# cndy-001.net
KiCad netlist of a schematic drawn in EAGLE
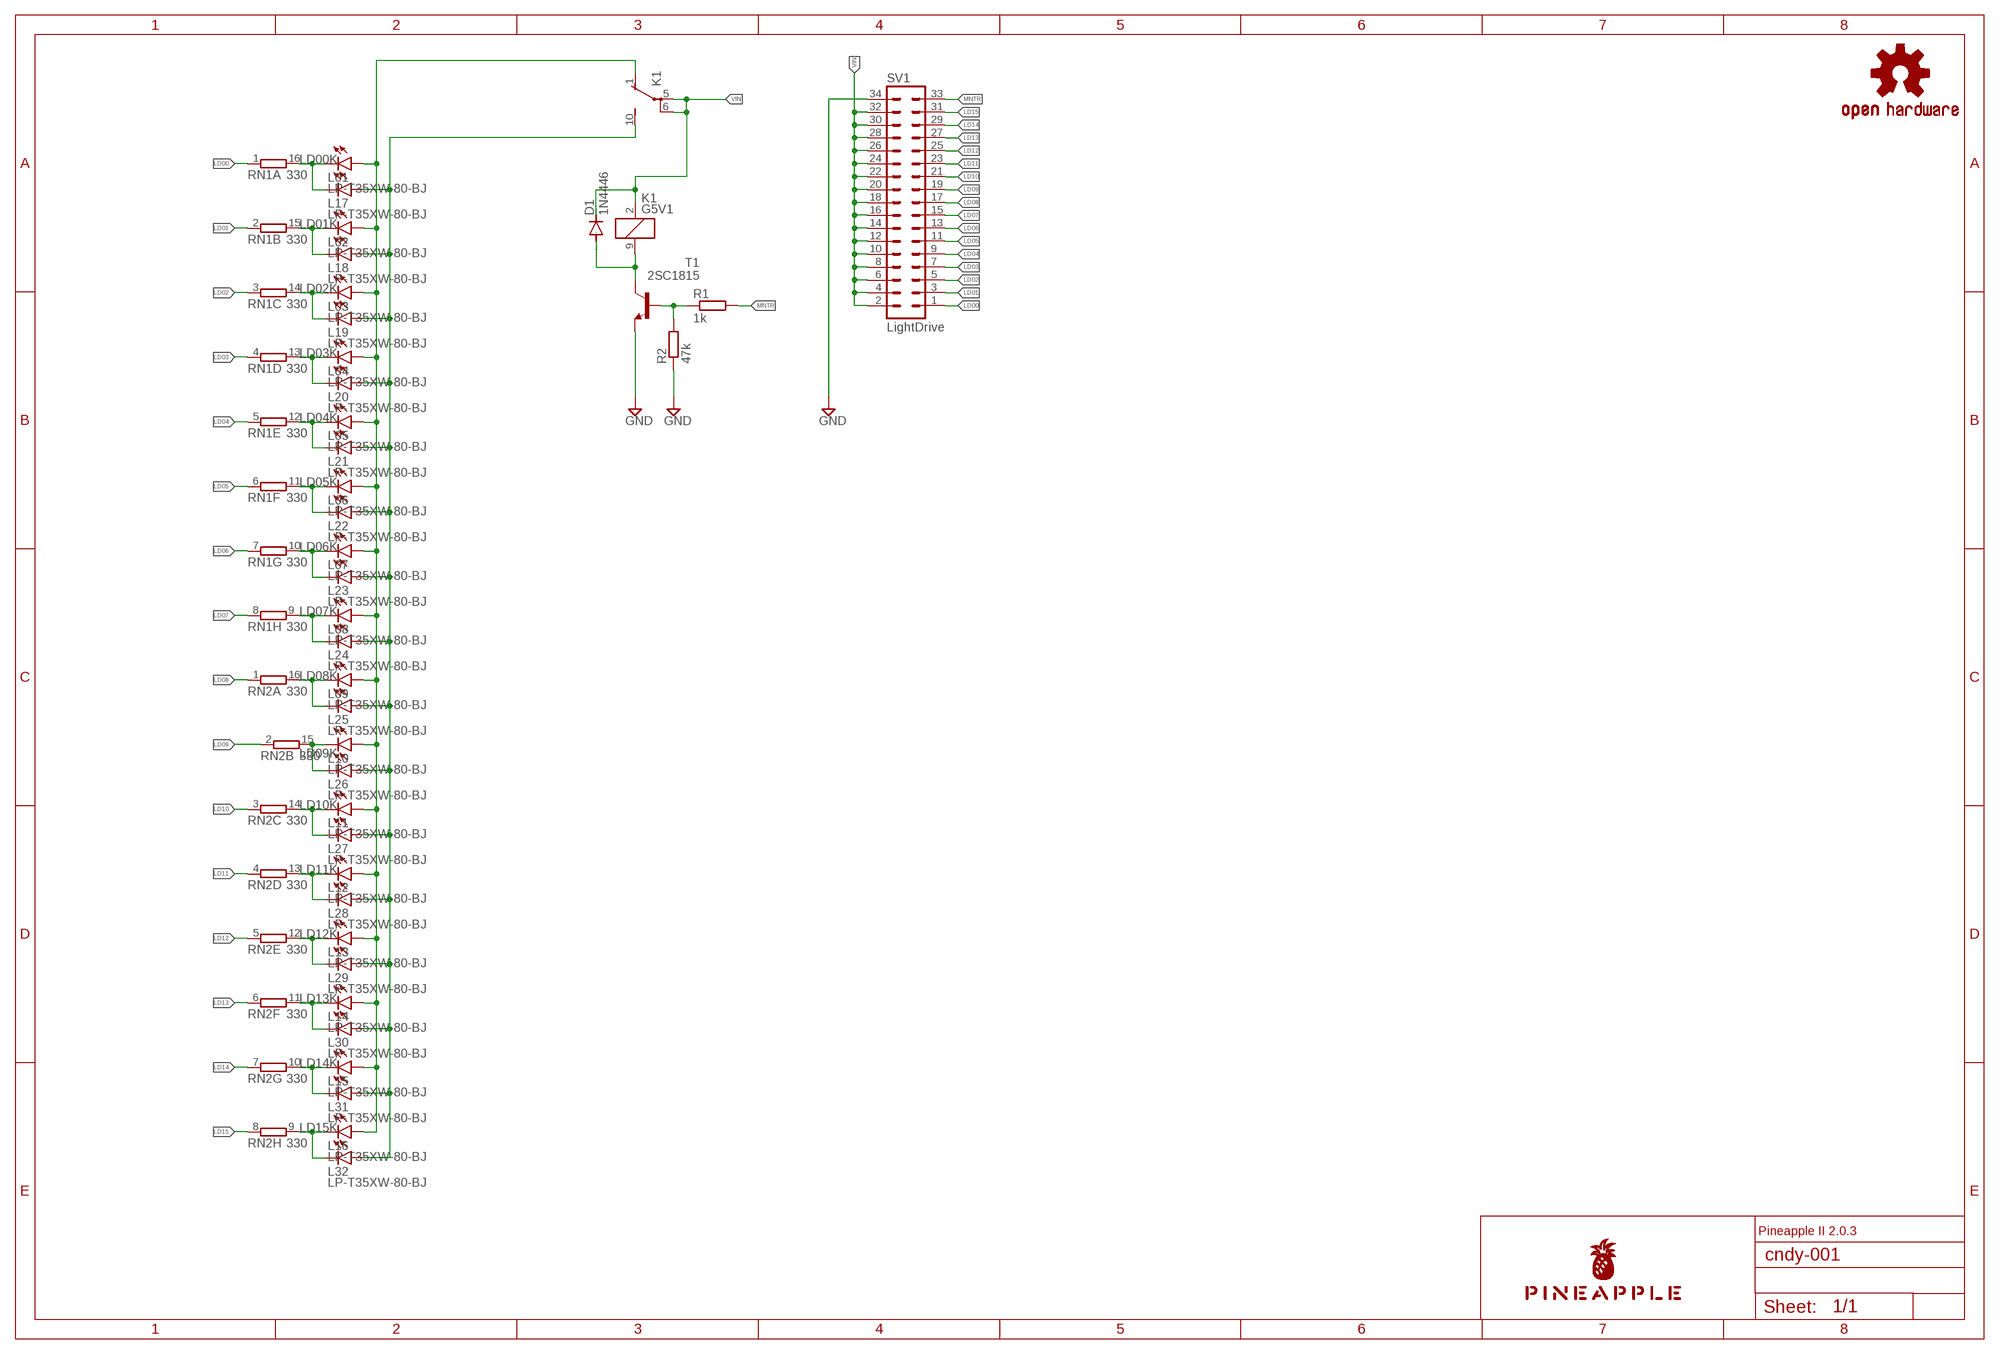
[diagram p0: schematic, sheet 1]

(export (version "E")
  (design (tool "Eeschema 10.0.6"))
  (components
    (comp (ref "D1")
      (value "1N4446")
      (footprint "eagle-import:DO35-10")
      (libsource (lib "eagle-import") (part "1N4446"))
    )
    (comp (ref "K1")
      (value "G5V1")
      (footprint "eagle-import:G5V1")
      (fields (field (name "MPN") "G5V-1-DC24"))
      (libsource (lib "eagle-import") (part "G5V1"))
    )
    (comp (ref "L01")
      (value "LP-T35XW-80-BJ")
      (footprint "eagle-import:KA-3528ASYC")
      (libsource (lib "eagle-import") (part "LEDKA-3528ASYC"))
    )
    (comp (ref "L02")
      (value "LP-T35XW-80-BJ")
      (footprint "eagle-import:KA-3528ASYC")
      (libsource (lib "eagle-import") (part "LEDKA-3528ASYC"))
    )
    (comp (ref "L03")
      (value "LP-T35XW-80-BJ")
      (footprint "eagle-import:KA-3528ASYC")
      (libsource (lib "eagle-import") (part "LEDKA-3528ASYC"))
    )
    (comp (ref "L04")
      (value "LP-T35XW-80-BJ")
      (footprint "eagle-import:KA-3528ASYC")
      (libsource (lib "eagle-import") (part "LEDKA-3528ASYC"))
    )
    (comp (ref "L05")
      (value "LP-T35XW-80-BJ")
      (footprint "eagle-import:KA-3528ASYC")
      (libsource (lib "eagle-import") (part "LEDKA-3528ASYC"))
    )
    (comp (ref "L06")
      (value "LP-T35XW-80-BJ")
      (footprint "eagle-import:KA-3528ASYC")
      (libsource (lib "eagle-import") (part "LEDKA-3528ASYC"))
    )
    (comp (ref "L07")
      (value "LP-T35XW-80-BJ")
      (footprint "eagle-import:KA-3528ASYC")
      (libsource (lib "eagle-import") (part "LEDKA-3528ASYC"))
    )
    (comp (ref "L08")
      (value "LP-T35XW-80-BJ")
      (footprint "eagle-import:KA-3528ASYC")
      (libsource (lib "eagle-import") (part "LEDKA-3528ASYC"))
    )
    (comp (ref "L09")
      (value "LP-T35XW-80-BJ")
      (footprint "eagle-import:KA-3528ASYC")
      (libsource (lib "eagle-import") (part "LEDKA-3528ASYC"))
    )
    (comp (ref "L10")
      (value "LP-T35XW-80-BJ")
      (footprint "eagle-import:KA-3528ASYC")
      (libsource (lib "eagle-import") (part "LEDKA-3528ASYC"))
    )
    (comp (ref "L11")
      (value "LP-T35XW-80-BJ")
      (footprint "eagle-import:KA-3528ASYC")
      (libsource (lib "eagle-import") (part "LEDKA-3528ASYC"))
    )
    (comp (ref "L12")
      (value "LP-T35XW-80-BJ")
      (footprint "eagle-import:KA-3528ASYC")
      (libsource (lib "eagle-import") (part "LEDKA-3528ASYC"))
    )
    (comp (ref "L13")
      (value "LP-T35XW-80-BJ")
      (footprint "eagle-import:KA-3528ASYC")
      (libsource (lib "eagle-import") (part "LEDKA-3528ASYC"))
    )
    (comp (ref "L14")
      (value "LP-T35XW-80-BJ")
      (footprint "eagle-import:KA-3528ASYC")
      (libsource (lib "eagle-import") (part "LEDKA-3528ASYC"))
    )
    (comp (ref "L15")
      (value "LP-T35XW-80-BJ")
      (footprint "eagle-import:KA-3528ASYC")
      (libsource (lib "eagle-import") (part "LEDKA-3528ASYC"))
    )
    (comp (ref "L16")
      (value "LP-T35XW-80-BJ")
      (footprint "eagle-import:KA-3528ASYC")
      (libsource (lib "eagle-import") (part "LEDKA-3528ASYC"))
    )
    (comp (ref "L17")
      (value "LP-T35XW-80-BJ")
      (footprint "eagle-import:KA-3528ASYC")
      (libsource (lib "eagle-import") (part "LEDKA-3528ASYC"))
    )
    (comp (ref "L18")
      (value "LP-T35XW-80-BJ")
      (footprint "eagle-import:KA-3528ASYC")
      (libsource (lib "eagle-import") (part "LEDKA-3528ASYC"))
    )
    (comp (ref "L19")
      (value "LP-T35XW-80-BJ")
      (footprint "eagle-import:KA-3528ASYC")
      (libsource (lib "eagle-import") (part "LEDKA-3528ASYC"))
    )
    (comp (ref "L20")
      (value "LP-T35XW-80-BJ")
      (footprint "eagle-import:KA-3528ASYC")
      (libsource (lib "eagle-import") (part "LEDKA-3528ASYC"))
    )
    (comp (ref "L21")
      (value "LP-T35XW-80-BJ")
      (footprint "eagle-import:KA-3528ASYC")
      (libsource (lib "eagle-import") (part "LEDKA-3528ASYC"))
    )
    (comp (ref "L22")
      (value "LP-T35XW-80-BJ")
      (footprint "eagle-import:KA-3528ASYC")
      (libsource (lib "eagle-import") (part "LEDKA-3528ASYC"))
    )
    (comp (ref "L23")
      (value "LP-T35XW-80-BJ")
      (footprint "eagle-import:KA-3528ASYC")
      (libsource (lib "eagle-import") (part "LEDKA-3528ASYC"))
    )
    (comp (ref "L24")
      (value "LP-T35XW-80-BJ")
      (footprint "eagle-import:KA-3528ASYC")
      (libsource (lib "eagle-import") (part "LEDKA-3528ASYC"))
    )
    (comp (ref "L25")
      (value "LP-T35XW-80-BJ")
      (footprint "eagle-import:KA-3528ASYC")
      (libsource (lib "eagle-import") (part "LEDKA-3528ASYC"))
    )
    (comp (ref "L26")
      (value "LP-T35XW-80-BJ")
      (footprint "eagle-import:KA-3528ASYC")
      (libsource (lib "eagle-import") (part "LEDKA-3528ASYC"))
    )
    (comp (ref "L27")
      (value "LP-T35XW-80-BJ")
      (footprint "eagle-import:KA-3528ASYC")
      (libsource (lib "eagle-import") (part "LEDKA-3528ASYC"))
    )
    (comp (ref "L28")
      (value "LP-T35XW-80-BJ")
      (footprint "eagle-import:KA-3528ASYC")
      (libsource (lib "eagle-import") (part "LEDKA-3528ASYC"))
    )
    (comp (ref "L29")
      (value "LP-T35XW-80-BJ")
      (footprint "eagle-import:KA-3528ASYC")
      (libsource (lib "eagle-import") (part "LEDKA-3528ASYC"))
    )
    (comp (ref "L30")
      (value "LP-T35XW-80-BJ")
      (footprint "eagle-import:KA-3528ASYC")
      (libsource (lib "eagle-import") (part "LEDKA-3528ASYC"))
    )
    (comp (ref "L31")
      (value "LP-T35XW-80-BJ")
      (footprint "eagle-import:KA-3528ASYC")
      (libsource (lib "eagle-import") (part "LEDKA-3528ASYC"))
    )
    (comp (ref "L32")
      (value "LP-T35XW-80-BJ")
      (footprint "eagle-import:KA-3528ASYC")
      (libsource (lib "eagle-import") (part "LEDKA-3528ASYC"))
    )
    (comp (ref "LOGO1")
      (value "OSHW-LOGOS-COPPER")
      (footprint "eagle-import:OSHW-LOGO-S_COPPER")
      (libsource (lib "eagle-import") (part "OSHW-LOGOS-COPPER"))
    )
    (comp (ref "R1")
      (value "1k")
      (footprint "eagle-import:0204_5")
      (libsource (lib "eagle-import") (part "R-EU_0204/5"))
    )
    (comp (ref "R2")
      (value "47k")
      (footprint "eagle-import:0204_5")
      (libsource (lib "eagle-import") (part "R-EU_0204/5"))
    )
    (comp (ref "RN1")
      (value "330")
      (footprint "eagle-import:DIL16")
      (libsource (lib "eagle-import") (part "8R-N"))
    )
    (comp (ref "RN2")
      (value "330")
      (footprint "eagle-import:DIL16")
      (libsource (lib "eagle-import") (part "8R-N"))
    )
    (comp (ref "SV1")
      (value "LightDrive")
      (footprint "eagle-import:ML34L")
      (libsource (lib "eagle-import") (part "ML34L"))
    )
    (comp (ref "T1")
      (value "2SC1815")
      (footprint "eagle-import:TO92-ECB")
      (libsource (lib "eagle-import") (part "2SC1815"))
    )
    (comp (ref "U$1")
      (value "PINEAPPLE450_SILK")
      (footprint "eagle-import:PINEAPPLE450_SILK")
      (libsource (lib "eagle-import") (part "PINEAPPLE450_SILK"))
    )
  )
  (nets
    (net (code "1") (name "/LD00K") (class "Default")
      (node (ref "L01") (pin "C") (pinfunction "C_C") (pintype "passive"))
      (node (ref "L17") (pin "C") (pinfunction "C_C") (pintype "passive"))
      (node (ref "RN1") (pin "16") (pinfunction "2_16") (pintype "passive"))
    )
    (net (code "2") (name "/LD01K") (class "Default")
      (node (ref "L02") (pin "C") (pinfunction "C_C") (pintype "passive"))
      (node (ref "L18") (pin "C") (pinfunction "C_C") (pintype "passive"))
      (node (ref "RN1") (pin "15") (pinfunction "2_15") (pintype "passive"))
    )
    (net (code "3") (name "/LD02K") (class "Default")
      (node (ref "L03") (pin "C") (pinfunction "C_C") (pintype "passive"))
      (node (ref "L19") (pin "C") (pinfunction "C_C") (pintype "passive"))
      (node (ref "RN1") (pin "14") (pinfunction "2_14") (pintype "passive"))
    )
    (net (code "4") (name "/LD03K") (class "Default")
      (node (ref "L04") (pin "C") (pinfunction "C_C") (pintype "passive"))
      (node (ref "L20") (pin "C") (pinfunction "C_C") (pintype "passive"))
      (node (ref "RN1") (pin "13") (pinfunction "2_13") (pintype "passive"))
    )
    (net (code "5") (name "/LD04K") (class "Default")
      (node (ref "L05") (pin "C") (pinfunction "C_C") (pintype "passive"))
      (node (ref "L21") (pin "C") (pinfunction "C_C") (pintype "passive"))
      (node (ref "RN1") (pin "12") (pinfunction "2_12") (pintype "passive"))
    )
    (net (code "6") (name "/LD05K") (class "Default")
      (node (ref "L06") (pin "C") (pinfunction "C_C") (pintype "passive"))
      (node (ref "L22") (pin "C") (pinfunction "C_C") (pintype "passive"))
      (node (ref "RN1") (pin "11") (pinfunction "2_11") (pintype "passive"))
    )
    (net (code "7") (name "/LD06K") (class "Default")
      (node (ref "L07") (pin "C") (pinfunction "C_C") (pintype "passive"))
      (node (ref "L23") (pin "C") (pinfunction "C_C") (pintype "passive"))
      (node (ref "RN1") (pin "10") (pinfunction "2_10") (pintype "passive"))
    )
    (net (code "8") (name "/LD07K") (class "Default")
      (node (ref "L08") (pin "C") (pinfunction "C_C") (pintype "passive"))
      (node (ref "L24") (pin "C") (pinfunction "C_C") (pintype "passive"))
      (node (ref "RN1") (pin "9") (pinfunction "2_9") (pintype "passive"))
    )
    (net (code "9") (name "/LD08K") (class "Default")
      (node (ref "L09") (pin "C") (pinfunction "C_C") (pintype "passive"))
      (node (ref "L25") (pin "C") (pinfunction "C_C") (pintype "passive"))
      (node (ref "RN2") (pin "16") (pinfunction "2_16") (pintype "passive"))
    )
    (net (code "10") (name "/LD09K") (class "Default")
      (node (ref "L10") (pin "C") (pinfunction "C_C") (pintype "passive"))
      (node (ref "L26") (pin "C") (pinfunction "C_C") (pintype "passive"))
      (node (ref "RN2") (pin "15") (pinfunction "2_15") (pintype "passive"))
    )
    (net (code "11") (name "/LD10K") (class "Default")
      (node (ref "L11") (pin "C") (pinfunction "C_C") (pintype "passive"))
      (node (ref "L27") (pin "C") (pinfunction "C_C") (pintype "passive"))
      (node (ref "RN2") (pin "14") (pinfunction "2_14") (pintype "passive"))
    )
    (net (code "12") (name "/LD11K") (class "Default")
      (node (ref "L12") (pin "C") (pinfunction "C_C") (pintype "passive"))
      (node (ref "L28") (pin "C") (pinfunction "C_C") (pintype "passive"))
      (node (ref "RN2") (pin "13") (pinfunction "2_13") (pintype "passive"))
    )
    (net (code "13") (name "/LD12K") (class "Default")
      (node (ref "L13") (pin "C") (pinfunction "C_C") (pintype "passive"))
      (node (ref "L29") (pin "C") (pinfunction "C_C") (pintype "passive"))
      (node (ref "RN2") (pin "12") (pinfunction "2_12") (pintype "passive"))
    )
    (net (code "14") (name "/LD13K") (class "Default")
      (node (ref "L14") (pin "C") (pinfunction "C_C") (pintype "passive"))
      (node (ref "L30") (pin "C") (pinfunction "C_C") (pintype "passive"))
      (node (ref "RN2") (pin "11") (pinfunction "2_11") (pintype "passive"))
    )
    (net (code "15") (name "/LD14K") (class "Default")
      (node (ref "L15") (pin "C") (pinfunction "C_C") (pintype "passive"))
      (node (ref "L31") (pin "C") (pinfunction "C_C") (pintype "passive"))
      (node (ref "RN2") (pin "10") (pinfunction "2_10") (pintype "passive"))
    )
    (net (code "16") (name "/LD15K") (class "Default")
      (node (ref "L16") (pin "C") (pinfunction "C_C") (pintype "passive"))
      (node (ref "L32") (pin "C") (pinfunction "C_C") (pintype "passive"))
      (node (ref "RN2") (pin "9") (pinfunction "2_9") (pintype "passive"))
    )
    (net (code "17") (name "GND") (class "Default")
      (node (ref "R2") (pin "1") (pinfunction "1_1") (pintype "passive"))
      (node (ref "SV1") (pin "34") (pinfunction "34_34") (pintype "passive"))
      (node (ref "T1") (pin "E") (pinfunction "E_E") (pintype "passive"))
    )
    (net (code "18") (name "LD00") (class "Default")
      (node (ref "RN1") (pin "1") (pinfunction "1_1") (pintype "passive"))
      (node (ref "SV1") (pin "1") (pinfunction "1_1") (pintype "passive"))
    )
    (net (code "19") (name "LD01") (class "Default")
      (node (ref "RN1") (pin "2") (pinfunction "1_2") (pintype "passive"))
      (node (ref "SV1") (pin "3") (pinfunction "3_3") (pintype "passive"))
    )
    (net (code "20") (name "LD02") (class "Default")
      (node (ref "RN1") (pin "3") (pinfunction "1_3") (pintype "passive"))
      (node (ref "SV1") (pin "5") (pinfunction "5_5") (pintype "passive"))
    )
    (net (code "21") (name "LD03") (class "Default")
      (node (ref "RN1") (pin "4") (pinfunction "1_4") (pintype "passive"))
      (node (ref "SV1") (pin "7") (pinfunction "7_7") (pintype "passive"))
    )
    (net (code "22") (name "LD04") (class "Default")
      (node (ref "RN1") (pin "5") (pinfunction "1_5") (pintype "passive"))
      (node (ref "SV1") (pin "9") (pinfunction "9_9") (pintype "passive"))
    )
    (net (code "23") (name "LD05") (class "Default")
      (node (ref "RN1") (pin "6") (pinfunction "1_6") (pintype "passive"))
      (node (ref "SV1") (pin "11") (pinfunction "11_11") (pintype "passive"))
    )
    (net (code "24") (name "LD06") (class "Default")
      (node (ref "RN1") (pin "7") (pinfunction "1_7") (pintype "passive"))
      (node (ref "SV1") (pin "13") (pinfunction "13_13") (pintype "passive"))
    )
    (net (code "25") (name "LD07") (class "Default")
      (node (ref "RN1") (pin "8") (pinfunction "1_8") (pintype "passive"))
      (node (ref "SV1") (pin "15") (pinfunction "15_15") (pintype "passive"))
    )
    (net (code "26") (name "LD08") (class "Default")
      (node (ref "RN2") (pin "1") (pinfunction "1_1") (pintype "passive"))
      (node (ref "SV1") (pin "17") (pinfunction "17_17") (pintype "passive"))
    )
    (net (code "27") (name "LD09") (class "Default")
      (node (ref "RN2") (pin "2") (pinfunction "1_2") (pintype "passive"))
      (node (ref "SV1") (pin "19") (pinfunction "19_19") (pintype "passive"))
    )
    (net (code "28") (name "LD10") (class "Default")
      (node (ref "RN2") (pin "3") (pinfunction "1_3") (pintype "passive"))
      (node (ref "SV1") (pin "21") (pinfunction "21_21") (pintype "passive"))
    )
    (net (code "29") (name "LD11") (class "Default")
      (node (ref "RN2") (pin "4") (pinfunction "1_4") (pintype "passive"))
      (node (ref "SV1") (pin "23") (pinfunction "23_23") (pintype "passive"))
    )
    (net (code "30") (name "LD12") (class "Default")
      (node (ref "RN2") (pin "5") (pinfunction "1_5") (pintype "passive"))
      (node (ref "SV1") (pin "25") (pinfunction "25_25") (pintype "passive"))
    )
    (net (code "31") (name "LD13") (class "Default")
      (node (ref "RN2") (pin "6") (pinfunction "1_6") (pintype "passive"))
      (node (ref "SV1") (pin "27") (pinfunction "27_27") (pintype "passive"))
    )
    (net (code "32") (name "LD14") (class "Default")
      (node (ref "RN2") (pin "7") (pinfunction "1_7") (pintype "passive"))
      (node (ref "SV1") (pin "29") (pinfunction "29_29") (pintype "passive"))
    )
    (net (code "33") (name "LD15") (class "Default")
      (node (ref "RN2") (pin "8") (pinfunction "1_8") (pintype "passive"))
      (node (ref "SV1") (pin "31") (pinfunction "31_31") (pintype "passive"))
    )
    (net (code "34") (name "MNTR") (class "Default")
      (node (ref "R1") (pin "2") (pinfunction "2_2") (pintype "passive"))
      (node (ref "SV1") (pin "33") (pinfunction "33_33") (pintype "passive"))
    )
    (net (code "35") (name "Net-(K1A-2)") (class "Default")
      (node (ref "D1") (pin "A") (pinfunction "A_A") (pintype "passive"))
      (node (ref "K1") (pin "9") (pinfunction "2_9") (pintype "passive"))
      (node (ref "T1") (pin "C") (pinfunction "C_C") (pintype "passive"))
    )
    (net (code "36") (name "Net-(K1B-O)") (class "Default")
      (node (ref "K1") (pin "1") (pinfunction "O_1") (pintype "passive"))
      (node (ref "L01") (pin "A") (pinfunction "A_A") (pintype "passive"))
      (node (ref "L02") (pin "A") (pinfunction "A_A") (pintype "passive"))
      (node (ref "L03") (pin "A") (pinfunction "A_A") (pintype "passive"))
      (node (ref "L04") (pin "A") (pinfunction "A_A") (pintype "passive"))
      (node (ref "L05") (pin "A") (pinfunction "A_A") (pintype "passive"))
      (node (ref "L06") (pin "A") (pinfunction "A_A") (pintype "passive"))
      (node (ref "L07") (pin "A") (pinfunction "A_A") (pintype "passive"))
      (node (ref "L08") (pin "A") (pinfunction "A_A") (pintype "passive"))
      (node (ref "L09") (pin "A") (pinfunction "A_A") (pintype "passive"))
      (node (ref "L10") (pin "A") (pinfunction "A_A") (pintype "passive"))
      (node (ref "L11") (pin "A") (pinfunction "A_A") (pintype "passive"))
      (node (ref "L12") (pin "A") (pinfunction "A_A") (pintype "passive"))
      (node (ref "L13") (pin "A") (pinfunction "A_A") (pintype "passive"))
      (node (ref "L14") (pin "A") (pinfunction "A_A") (pintype "passive"))
      (node (ref "L15") (pin "A") (pinfunction "A_A") (pintype "passive"))
      (node (ref "L16") (pin "A") (pinfunction "A_A") (pintype "passive"))
    )
    (net (code "37") (name "Net-(K1B-S)") (class "Default")
      (node (ref "K1") (pin "10") (pinfunction "S_10") (pintype "passive"))
      (node (ref "L17") (pin "A") (pinfunction "A_A") (pintype "passive"))
      (node (ref "L18") (pin "A") (pinfunction "A_A") (pintype "passive"))
      (node (ref "L19") (pin "A") (pinfunction "A_A") (pintype "passive"))
      (node (ref "L20") (pin "A") (pinfunction "A_A") (pintype "passive"))
      (node (ref "L21") (pin "A") (pinfunction "A_A") (pintype "passive"))
      (node (ref "L22") (pin "A") (pinfunction "A_A") (pintype "passive"))
      (node (ref "L23") (pin "A") (pinfunction "A_A") (pintype "passive"))
      (node (ref "L24") (pin "A") (pinfunction "A_A") (pintype "passive"))
      (node (ref "L25") (pin "A") (pinfunction "A_A") (pintype "passive"))
      (node (ref "L26") (pin "A") (pinfunction "A_A") (pintype "passive"))
      (node (ref "L27") (pin "A") (pinfunction "A_A") (pintype "passive"))
      (node (ref "L28") (pin "A") (pinfunction "A_A") (pintype "passive"))
      (node (ref "L29") (pin "A") (pinfunction "A_A") (pintype "passive"))
      (node (ref "L30") (pin "A") (pinfunction "A_A") (pintype "passive"))
      (node (ref "L31") (pin "A") (pinfunction "A_A") (pintype "passive"))
      (node (ref "L32") (pin "A") (pinfunction "A_A") (pintype "passive"))
    )
    (net (code "38") (name "Net-(R1-Pad1)") (class "Default")
      (node (ref "R1") (pin "1") (pinfunction "1_1") (pintype "passive"))
      (node (ref "R2") (pin "2") (pinfunction "2_2") (pintype "passive"))
      (node (ref "T1") (pin "B") (pinfunction "B_B") (pintype "passive"))
    )
    (net (code "39") (name "VIN") (class "Default")
      (node (ref "D1") (pin "C") (pinfunction "C_C") (pintype "passive"))
      (node (ref "K1") (pin "2") (pinfunction "1_2") (pintype "passive"))
      (node (ref "K1") (pin "5") (pinfunction "P_5") (pintype "passive"))
      (node (ref "K1") (pin "6") (pinfunction "P_6") (pintype "passive"))
      (node (ref "SV1") (pin "10") (pinfunction "10_10") (pintype "passive"))
      (node (ref "SV1") (pin "12") (pinfunction "12_12") (pintype "passive"))
      (node (ref "SV1") (pin "14") (pinfunction "14_14") (pintype "passive"))
      (node (ref "SV1") (pin "16") (pinfunction "16_16") (pintype "passive"))
      (node (ref "SV1") (pin "18") (pinfunction "18_18") (pintype "passive"))
      (node (ref "SV1") (pin "2") (pinfunction "2_2") (pintype "passive"))
      (node (ref "SV1") (pin "20") (pinfunction "20_20") (pintype "passive"))
      (node (ref "SV1") (pin "22") (pinfunction "22_22") (pintype "passive"))
      (node (ref "SV1") (pin "24") (pinfunction "24_24") (pintype "passive"))
      (node (ref "SV1") (pin "26") (pinfunction "26_26") (pintype "passive"))
      (node (ref "SV1") (pin "28") (pinfunction "28_28") (pintype "passive"))
      (node (ref "SV1") (pin "30") (pinfunction "30_30") (pintype "passive"))
      (node (ref "SV1") (pin "32") (pinfunction "32_32") (pintype "passive"))
      (node (ref "SV1") (pin "4") (pinfunction "4_4") (pintype "passive"))
      (node (ref "SV1") (pin "6") (pinfunction "6_6") (pintype "passive"))
      (node (ref "SV1") (pin "8") (pinfunction "8_8") (pintype "passive"))
    )
  )
)
